# interface_b.net
KiCad netlist of a schematic drawn in EAGLE
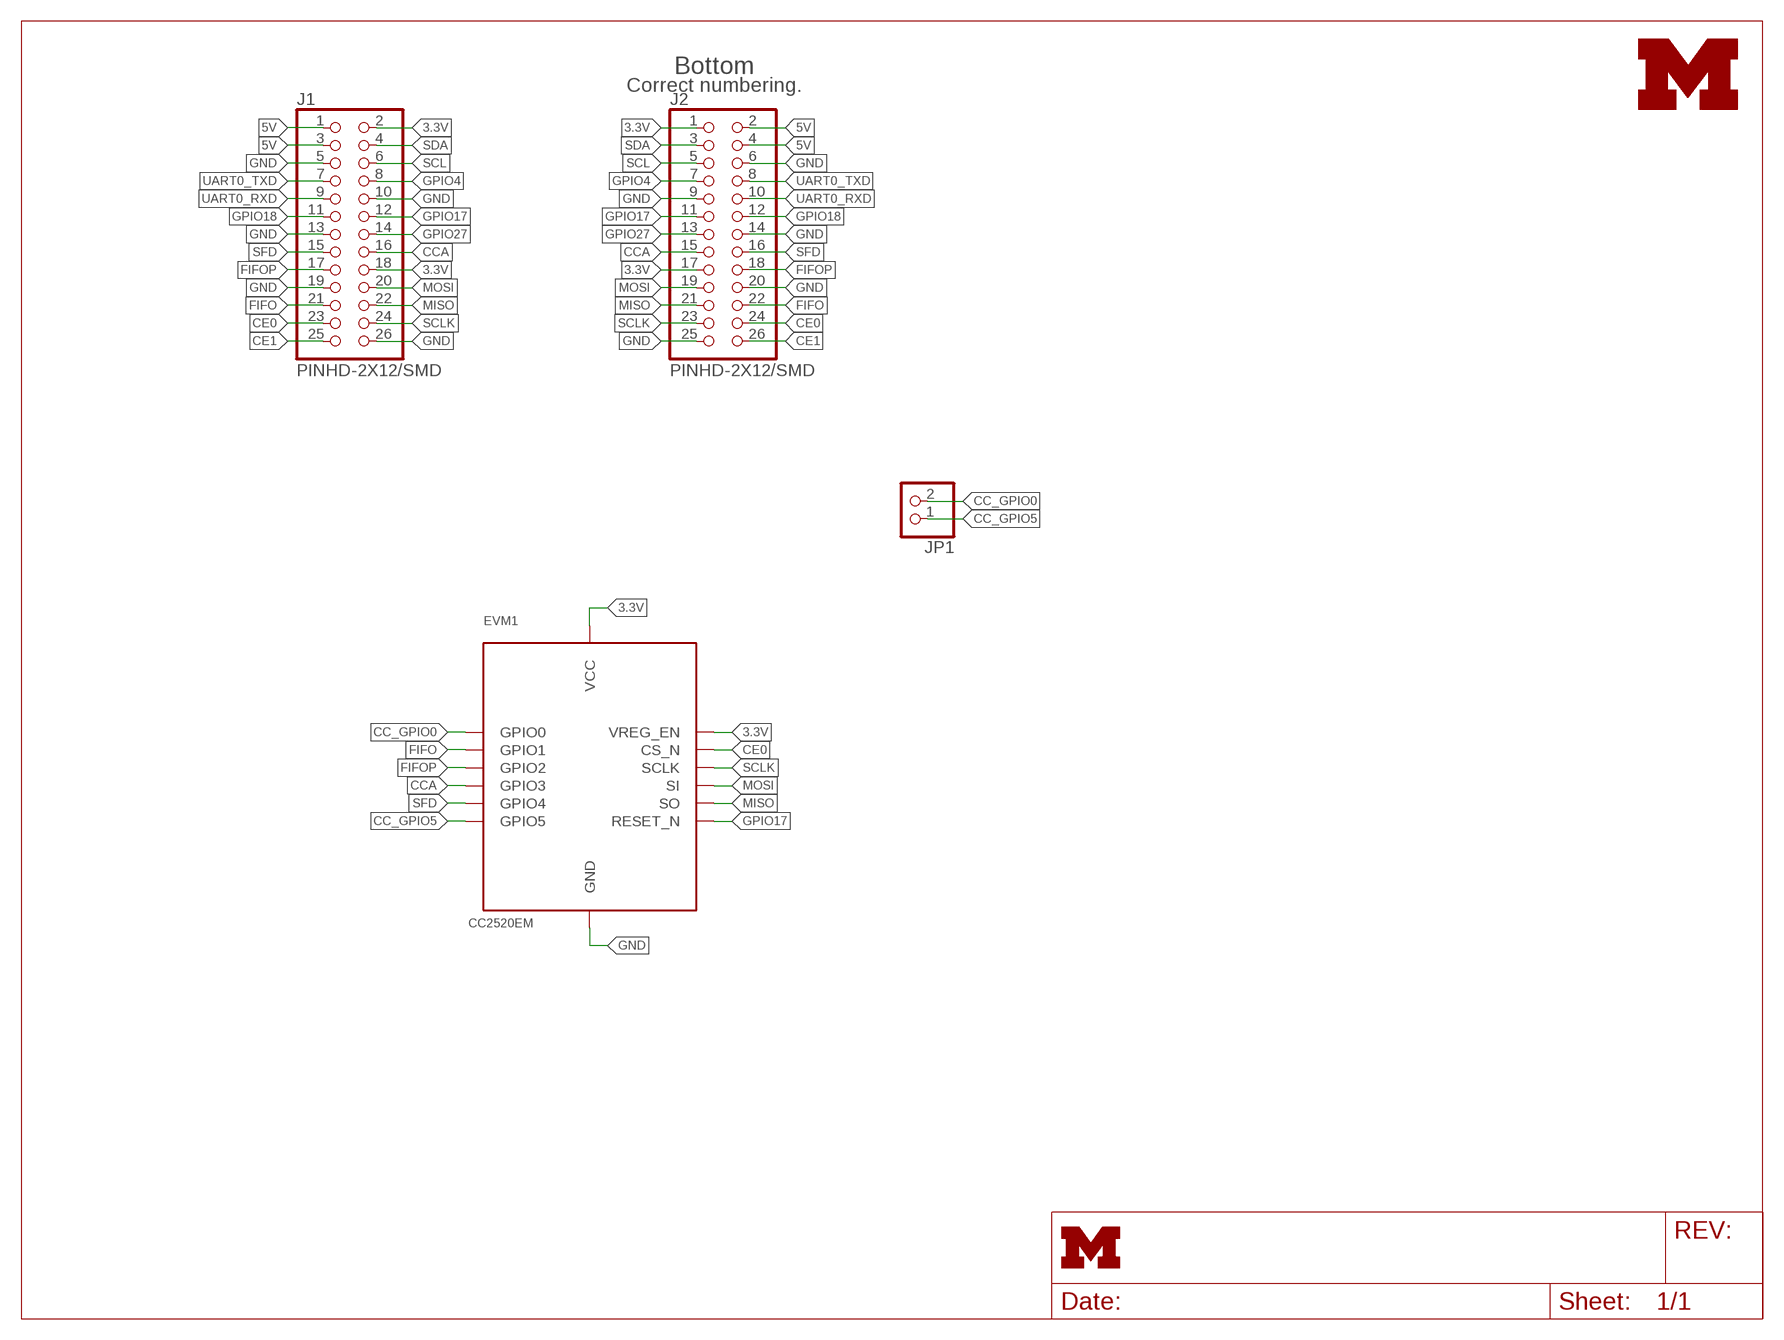
[diagram p0: schematic, sheet 1]

(export (version "E")
  (design (tool "Eeschema 10.0.6"))
  (components
    (comp (ref "EVM1")
      (value "CC2520EM")
      (footprint "eagle-import:TI_CC_EVM")
      (libsource (lib "eagle-import") (part "CC2520EM"))
    )
    (comp (ref "J1")
      (value "PINHD-2X12/SMD")
      (footprint "eagle-import:2X13_SMD")
      (libsource (lib "eagle-import") (part "PINHD-2X12/SMD"))
    )
    (comp (ref "J2")
      (value "PINHD-2X12/SMD")
      (footprint "eagle-import:2X13_SMD")
      (libsource (lib "eagle-import") (part "PINHD-2X12/SMD"))
    )
    (comp (ref "JP1")
      (value "PINHD-1X2")
      (footprint "eagle-import:1X02")
      (libsource (lib "eagle-import") (part "PINHD-1X2"))
    )
    (comp (ref "U$1")
      (value "UMICH_SOLID_SMALL")
      (footprint "eagle-import:UMICH_SOLID_75MIL")
      (libsource (lib "eagle-import") (part "UMICH_SOLID_SMALL"))
    )
  )
  (nets
    (net (code "1") (name "3.3V") (class "Default")
      (node (ref "EVM1") (pin "P1_10") (pinfunction "VREG_EN_P1_10") (pintype "bidirectional"))
      (node (ref "EVM1") (pin "P2_7") (pinfunction "VCC_P2_7") (pintype "bidirectional"))
      (node (ref "EVM1") (pin "P2_9") (pinfunction "VCC_P2_9") (pintype "bidirectional"))
      (node (ref "J1") (pin "18") (pinfunction "18_18") (pintype "passive"))
      (node (ref "J1") (pin "2") (pinfunction "2_2") (pintype "passive"))
      (node (ref "J2") (pin "1") (pinfunction "1_1") (pintype "passive"))
      (node (ref "J2") (pin "17") (pinfunction "17_17") (pintype "passive"))
    )
    (net (code "2") (name "5V") (class "Default")
      (node (ref "J1") (pin "1") (pinfunction "1_1") (pintype "passive"))
      (node (ref "J1") (pin "3") (pinfunction "3_3") (pintype "passive"))
      (node (ref "J2") (pin "2") (pinfunction "2_2") (pintype "passive"))
      (node (ref "J2") (pin "4") (pinfunction "4_4") (pintype "passive"))
    )
    (net (code "3") (name "CCA") (class "Default")
      (node (ref "EVM1") (pin "P1_12") (pinfunction "GPIO3_P1_12") (pintype "bidirectional"))
      (node (ref "J1") (pin "16") (pinfunction "16_16") (pintype "passive"))
      (node (ref "J2") (pin "15") (pinfunction "15_15") (pintype "passive"))
    )
    (net (code "4") (name "CC_GPIO0") (class "Default")
      (node (ref "EVM1") (pin "P1_3") (pinfunction "GPIO0_P1_3") (pintype "bidirectional"))
      (node (ref "JP1") (pin "2") (pinfunction "2_2") (pintype "passive"))
    )
    (net (code "5") (name "CC_GPIO5") (class "Default")
      (node (ref "EVM1") (pin "P2_19") (pinfunction "GPIO5_P2_19") (pintype "bidirectional"))
      (node (ref "JP1") (pin "1") (pinfunction "1_1") (pintype "passive"))
    )
    (net (code "6") (name "CE0") (class "Default")
      (node (ref "EVM1") (pin "P1_14") (pinfunction "CS_N_P1_14") (pintype "bidirectional"))
      (node (ref "J1") (pin "23") (pinfunction "23_23") (pintype "passive"))
      (node (ref "J2") (pin "24") (pinfunction "24_24") (pintype "passive"))
    )
    (net (code "7") (name "CE1") (class "Default")
      (node (ref "J1") (pin "25") (pinfunction "25_25") (pintype "passive"))
      (node (ref "J2") (pin "26") (pinfunction "26_26") (pintype "passive"))
    )
    (net (code "8") (name "FIFO") (class "Default")
      (node (ref "EVM1") (pin "P1_7") (pinfunction "GPIO1_P1_7") (pintype "bidirectional"))
      (node (ref "J1") (pin "21") (pinfunction "21_21") (pintype "passive"))
      (node (ref "J2") (pin "22") (pinfunction "22_22") (pintype "passive"))
    )
    (net (code "9") (name "FIFOP") (class "Default")
      (node (ref "EVM1") (pin "P1_9") (pinfunction "GPIO2_P1_9") (pintype "bidirectional"))
      (node (ref "J1") (pin "17") (pinfunction "17_17") (pintype "passive"))
      (node (ref "J2") (pin "18") (pinfunction "18_18") (pintype "passive"))
    )
    (net (code "10") (name "GND") (class "Default")
      (node (ref "EVM1") (pin "P1_1") (pinfunction "GND_P1_1") (pintype "bidirectional"))
      (node (ref "EVM1") (pin "P1_19") (pinfunction "GND_P1_19") (pintype "bidirectional"))
      (node (ref "J1") (pin "10") (pinfunction "10_10") (pintype "passive"))
      (node (ref "J1") (pin "13") (pinfunction "13_13") (pintype "passive"))
      (node (ref "J1") (pin "19") (pinfunction "19_19") (pintype "passive"))
      (node (ref "J1") (pin "26") (pinfunction "26_26") (pintype "passive"))
      (node (ref "J1") (pin "5") (pinfunction "5_5") (pintype "passive"))
      (node (ref "J2") (pin "14") (pinfunction "14_14") (pintype "passive"))
      (node (ref "J2") (pin "20") (pinfunction "20_20") (pintype "passive"))
      (node (ref "J2") (pin "25") (pinfunction "25_25") (pintype "passive"))
      (node (ref "J2") (pin "6") (pinfunction "6_6") (pintype "passive"))
      (node (ref "J2") (pin "9") (pinfunction "9_9") (pintype "passive"))
    )
    (net (code "11") (name "GPIO4") (class "Default")
      (node (ref "J1") (pin "8") (pinfunction "8_8") (pintype "passive"))
      (node (ref "J2") (pin "7") (pinfunction "7_7") (pintype "passive"))
    )
    (net (code "12") (name "GPIO17") (class "Default")
      (node (ref "EVM1") (pin "P2_15") (pinfunction "RESET_N_P2_15") (pintype "bidirectional"))
      (node (ref "J1") (pin "12") (pinfunction "12_12") (pintype "passive"))
      (node (ref "J2") (pin "11") (pinfunction "11_11") (pintype "passive"))
    )
    (net (code "13") (name "GPIO18") (class "Default")
      (node (ref "J1") (pin "11") (pinfunction "11_11") (pintype "passive"))
      (node (ref "J2") (pin "12") (pinfunction "12_12") (pintype "passive"))
    )
    (net (code "14") (name "GPIO27") (class "Default")
      (node (ref "J1") (pin "14") (pinfunction "14_14") (pintype "passive"))
      (node (ref "J2") (pin "13") (pinfunction "13_13") (pintype "passive"))
    )
    (net (code "15") (name "MISO") (class "Default")
      (node (ref "EVM1") (pin "P1_20") (pinfunction "SO_P1_20") (pintype "bidirectional"))
      (node (ref "J1") (pin "22") (pinfunction "22_22") (pintype "passive"))
      (node (ref "J2") (pin "21") (pinfunction "21_21") (pintype "passive"))
    )
    (net (code "16") (name "MOSI") (class "Default")
      (node (ref "EVM1") (pin "P1_18") (pinfunction "SI_P1_18") (pintype "bidirectional"))
      (node (ref "J1") (pin "20") (pinfunction "20_20") (pintype "passive"))
      (node (ref "J2") (pin "19") (pinfunction "19_19") (pintype "passive"))
    )
    (net (code "17") (name "SCL") (class "Default")
      (node (ref "J1") (pin "6") (pinfunction "6_6") (pintype "passive"))
      (node (ref "J2") (pin "5") (pinfunction "5_5") (pintype "passive"))
    )
    (net (code "18") (name "SCLK") (class "Default")
      (node (ref "EVM1") (pin "P1_16") (pinfunction "SCLK_P1_16") (pintype "bidirectional"))
      (node (ref "J1") (pin "24") (pinfunction "24_24") (pintype "passive"))
      (node (ref "J2") (pin "23") (pinfunction "23_23") (pintype "passive"))
    )
    (net (code "19") (name "SDA") (class "Default")
      (node (ref "J1") (pin "4") (pinfunction "4_4") (pintype "passive"))
      (node (ref "J2") (pin "3") (pinfunction "3_3") (pintype "passive"))
    )
    (net (code "20") (name "SFD") (class "Default")
      (node (ref "EVM1") (pin "P2_18") (pinfunction "GPIO4_P2_18") (pintype "bidirectional"))
      (node (ref "J1") (pin "15") (pinfunction "15_15") (pintype "passive"))
      (node (ref "J2") (pin "16") (pinfunction "16_16") (pintype "passive"))
    )
    (net (code "21") (name "UART0_RXD") (class "Default")
      (node (ref "J1") (pin "9") (pinfunction "9_9") (pintype "passive"))
      (node (ref "J2") (pin "10") (pinfunction "10_10") (pintype "passive"))
    )
    (net (code "22") (name "UART0_TXD") (class "Default")
      (node (ref "J1") (pin "7") (pinfunction "7_7") (pintype "passive"))
      (node (ref "J2") (pin "8") (pinfunction "8_8") (pintype "passive"))
    )
  )
)
